# battery_board_main.net
KiCad netlist of a schematic drawn in EAGLE
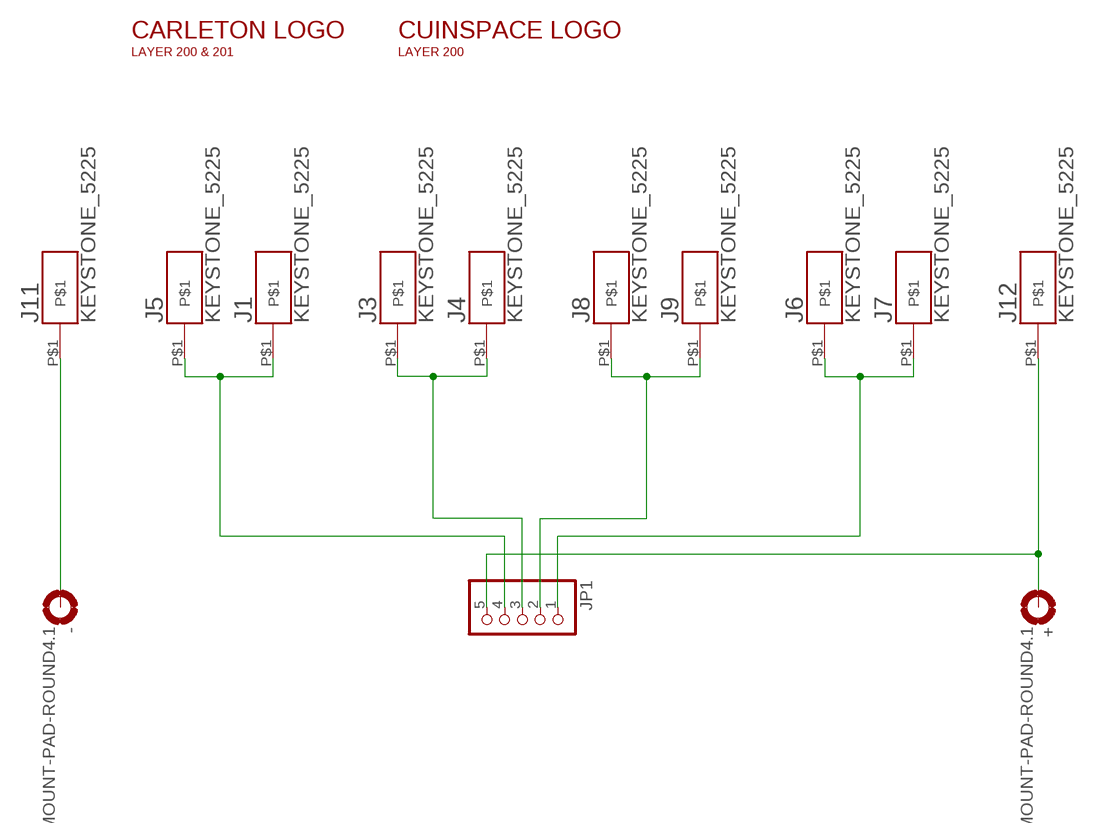
[diagram p0: schematic, sheet 1]

(export (version "E")
  (design (tool "Eeschema 10.0.6"))
  (components
    (comp (ref "+")
      (value "MOUNT-PAD-ROUND4.1")
      (footprint "eagle-import:4,1-PAD")
      (libsource (lib "eagle-import") (part "MOUNT-PAD-ROUND4.1"))
    )
    (comp (ref "-")
      (value "MOUNT-PAD-ROUND4.1")
      (footprint "eagle-import:4,1-PAD")
      (libsource (lib "eagle-import") (part "MOUNT-PAD-ROUND4.1"))
    )
    (comp (ref "J1")
      (value "KEYSTONE_5225")
      (footprint "eagle-import:KEYSTONE_5225")
      (libsource (lib "eagle-import") (part "KEYSTONE_5225"))
    )
    (comp (ref "J3")
      (value "KEYSTONE_5225")
      (footprint "eagle-import:KEYSTONE_5225")
      (libsource (lib "eagle-import") (part "KEYSTONE_5225"))
    )
    (comp (ref "J4")
      (value "KEYSTONE_5225")
      (footprint "eagle-import:KEYSTONE_5225")
      (libsource (lib "eagle-import") (part "KEYSTONE_5225"))
    )
    (comp (ref "J5")
      (value "KEYSTONE_5225")
      (footprint "eagle-import:KEYSTONE_5225")
      (libsource (lib "eagle-import") (part "KEYSTONE_5225"))
    )
    (comp (ref "J6")
      (value "KEYSTONE_5225")
      (footprint "eagle-import:KEYSTONE_5225")
      (libsource (lib "eagle-import") (part "KEYSTONE_5225"))
    )
    (comp (ref "J7")
      (value "KEYSTONE_5225")
      (footprint "eagle-import:KEYSTONE_5225")
      (libsource (lib "eagle-import") (part "KEYSTONE_5225"))
    )
    (comp (ref "J8")
      (value "KEYSTONE_5225")
      (footprint "eagle-import:KEYSTONE_5225")
      (libsource (lib "eagle-import") (part "KEYSTONE_5225"))
    )
    (comp (ref "J9")
      (value "KEYSTONE_5225")
      (footprint "eagle-import:KEYSTONE_5225")
      (libsource (lib "eagle-import") (part "KEYSTONE_5225"))
    )
    (comp (ref "J11")
      (value "KEYSTONE_5225")
      (footprint "eagle-import:KEYSTONE_5225")
      (libsource (lib "eagle-import") (part "KEYSTONE_5225"))
    )
    (comp (ref "J12")
      (value "KEYSTONE_5225")
      (footprint "eagle-import:KEYSTONE_5225")
      (libsource (lib "eagle-import") (part "KEYSTONE_5225"))
    )
    (comp (ref "JP1")
      (value "PINHD-1X5")
      (footprint "eagle-import:1X05")
      (libsource (lib "eagle-import") (part "PINHD-1X5"))
    )
    (comp (ref "U$1")
      (value "CARLETON3CM")
      (footprint "eagle-import:CARLETONU_3CM")
      (libsource (lib "eagle-import") (part "CARLETON3CM"))
    )
    (comp (ref "U$2")
      (value "INSPACE3CM")
      (footprint "eagle-import:INSPACE_3CM")
      (libsource (lib "eagle-import") (part "INSPACE3CM"))
    )
  )
  (nets
    (net (code "1") (name "Net-(+-MOUNT)") (class "Default")
      (node (ref "+") (pin "B4,1") (pinfunction "MOUNT_B4,1") (pintype "passive"))
      (node (ref "J12") (pin "P$1") (pinfunction "P$1_P$1") (pintype "bidirectional"))
      (node (ref "JP1") (pin "5") (pinfunction "5_5") (pintype "passive"))
    )
    (net (code "2") (name "Net-(--MOUNT)") (class "Default")
      (node (ref "-") (pin "B4,1") (pinfunction "MOUNT_B4,1") (pintype "passive"))
      (node (ref "J11") (pin "P$1") (pinfunction "P$1_P$1") (pintype "bidirectional"))
    )
    (net (code "3") (name "Net-(J1-PadP$1)") (class "Default")
      (node (ref "J1") (pin "P$1") (pinfunction "P$1_P$1") (pintype "bidirectional"))
      (node (ref "J5") (pin "P$1") (pinfunction "P$1_P$1") (pintype "bidirectional"))
      (node (ref "JP1") (pin "4") (pinfunction "4_4") (pintype "passive"))
    )
    (net (code "4") (name "Net-(J3-PadP$1)") (class "Default")
      (node (ref "J3") (pin "P$1") (pinfunction "P$1_P$1") (pintype "bidirectional"))
      (node (ref "J4") (pin "P$1") (pinfunction "P$1_P$1") (pintype "bidirectional"))
      (node (ref "JP1") (pin "3") (pinfunction "3_3") (pintype "passive"))
    )
    (net (code "5") (name "Net-(J6-PadP$1)") (class "Default")
      (node (ref "J6") (pin "P$1") (pinfunction "P$1_P$1") (pintype "bidirectional"))
      (node (ref "J7") (pin "P$1") (pinfunction "P$1_P$1") (pintype "bidirectional"))
      (node (ref "JP1") (pin "1") (pinfunction "1_1") (pintype "passive"))
    )
    (net (code "6") (name "Net-(J8-PadP$1)") (class "Default")
      (node (ref "J8") (pin "P$1") (pinfunction "P$1_P$1") (pintype "bidirectional"))
      (node (ref "J9") (pin "P$1") (pinfunction "P$1_P$1") (pintype "bidirectional"))
      (node (ref "JP1") (pin "2") (pinfunction "2_2") (pintype "passive"))
    )
  )
)
